# Overcurrent_Protection.net
KiCad netlist of a schematic drawn in Altium Designer
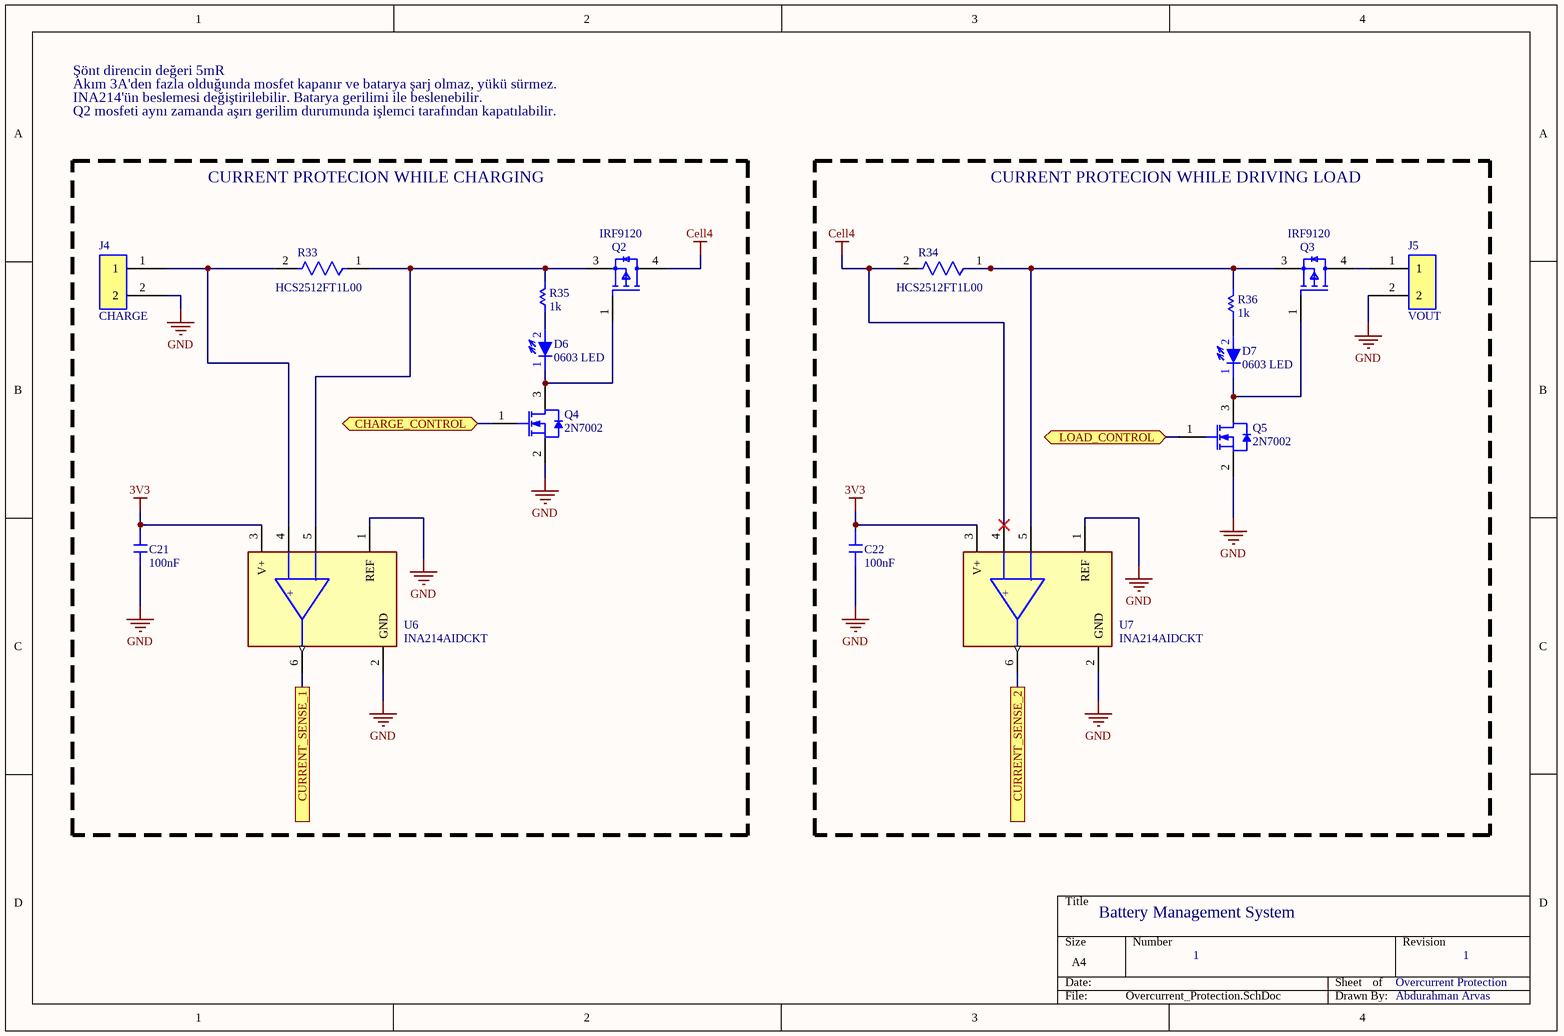
[diagram p0: Overcurrent_Protection.SchDoc]

(export (version "E")
  (design (tool "Eeschema 10.0.6"))
  (components
    (comp (ref "C21")
      (value "100nF")
      (footprint "C0805")
      (libsource (lib "Arvas_AltiumSCH") (part "SMD_Capacitor"))
    )
    (comp (ref "C22")
      (value "100nF")
      (footprint "C0805")
      (libsource (lib "Arvas_AltiumSCH") (part "SMD_Capacitor"))
    )
    (comp (ref "D6")
      (value "0603 LED")
      (footprint "LED_0603")
      (description "Light Emitting Diode with 0603 footprint.")
      (libsource (lib "Arvas_AltiumSCH") (part "Led 0603"))
    )
    (comp (ref "D7")
      (value "0603 LED")
      (footprint "LED_0603")
      (description "Light Emitting Diode with 0603 footprint.")
      (libsource (lib "Arvas_AltiumSCH") (part "Led 0603"))
    )
    (comp (ref "J4")
      (value "CHARGE")
      (footprint "CONN X2")
      (description "İki Pin Connector")
      (libsource (lib "Arvas_AltiumSCH") (part "CONN X2"))
    )
    (comp (ref "J5")
      (value "VOUT")
      (footprint "CONN X2")
      (description "İki Pin Connector")
      (libsource (lib "Arvas_AltiumSCH") (part "CONN X2"))
    )
    (comp (ref "Q2")
      (value "IRF9120")
      (footprint "FP-TO-252-MFG")
      (description "MOSFET P-CHANNEL 60V 20A TO252")
      (libsource (lib "Altium Content Vault") (part "20f9a20c5713cc6515f41ebd1ff0572"))
    )
    (comp (ref "Q3")
      (value "IRF9120")
      (footprint "FP-TO-252-MFG")
      (description "MOSFET P-CHANNEL 60V 20A TO252")
      (libsource (lib "Altium Content Vault") (part "20f9a20c5713cc6515f41ebd1ff0572"))
    )
    (comp (ref "Q4")
      (value "2N7002")
      (footprint "STM-SOT-23-3_V")
      (description "N-channel 60 V, 1.8 Ohm, 0.35 A STripFET(TM) II Power MOSFET, SOT23")
      (fields (field (name "MANUFACTURER") "STMicroelectronics"))
      (libsource (lib "Altium Content Vault") (part "STM-NEMOS-G1S2D3-3"))
    )
    (comp (ref "Q5")
      (value "2N7002")
      (footprint "STM-SOT-23-3_V")
      (description "N-channel 60 V, 1.8 Ohm, 0.35 A STripFET(TM) II Power MOSFET, SOT23")
      (fields (field (name "MANUFACTURER") "STMicroelectronics"))
      (libsource (lib "Altium Content Vault") (part "STM-NEMOS-G1S2D3-3"))
    )
    (comp (ref "R33")
      (value "HCS2512FT1L00")
      (footprint "FP-HCS2512FT1L00-MFG")
      (description "RES 0.001 OHM 1% 3W 2512")
      (fields (field (name "TOLERANCE") "1%"))
      (libsource (lib "Altium Content Vault") (part "1029c3af85768c4190bb7ad29bc67b5"))
    )
    (comp (ref "R34")
      (value "HCS2512FT1L00")
      (footprint "FP-HCS2512FT1L00-MFG")
      (description "RES 0.001 OHM 1% 3W 2512")
      (fields (field (name "TOLERANCE") "1%"))
      (libsource (lib "Altium Content Vault") (part "1029c3af85768c4190bb7ad29bc67b5"))
    )
    (comp (ref "R35")
      (value "1k")
      (footprint "R0805")
      (description "SMD Chip Resistor")
      (libsource (lib "Arvas_AltiumSCH") (part "SMD Resistor"))
    )
    (comp (ref "R36")
      (value "1k")
      (footprint "R0805")
      (description "SMD Chip Resistor")
      (libsource (lib "Arvas_AltiumSCH") (part "SMD Resistor"))
    )
    (comp (ref "U6")
      (value "INA214AIDCKT")
      (footprint "FP-DCK0006A-MFG")
      (description "IC CURR SENSE 1 CIRCUIT SC70-6")
      (fields
        (field (name "MANUFACTURER") "Texas Instruments")
        (field (name "OCTOPART") "https://octopart.com/ina214aidckt-texas+instruments-7830703")
      )
      (libsource (lib "Altium Content Vault") (part "c10d82c028949ab116d50aa41bcba86"))
    )
    (comp (ref "U7")
      (value "INA214AIDCKT")
      (footprint "FP-DCK0006A-MFG")
      (description "IC CURR SENSE 1 CIRCUIT SC70-6")
      (fields
        (field (name "MANUFACTURER") "Texas Instruments")
        (field (name "OCTOPART") "https://octopart.com/ina214aidckt-texas+instruments-7830703")
      )
      (libsource (lib "Altium Content Vault") (part "c10d82c028949ab116d50aa41bcba86"))
    )
  )
  (nets
    (net (code "1") (name "/CHARGE_CONTROL") (class "Default")
      (node (ref "Q4") (pin "1") (pinfunction "G_1") (pintype "passive"))
    )
    (net (code "2") (name "/CURRENT_SENSE_1") (class "Default")
      (node (ref "U6") (pin "6") (pinfunction "OUT_6") (pintype "output"))
    )
    (net (code "3") (name "/CURRENT_SENSE_2") (class "Default")
      (node (ref "U7") (pin "6") (pinfunction "OUT_6") (pintype "output"))
    )
    (net (code "4") (name "/LOAD_CONTROL") (class "Default")
      (node (ref "Q5") (pin "1") (pinfunction "G_1") (pintype "passive"))
    )
    (net (code "5") (name "3V3") (class "Default")
      (node (ref "C21") (pin "2") (pinfunction "2_2") (pintype "passive"))
      (node (ref "C22") (pin "2") (pinfunction "2_2") (pintype "passive"))
      (node (ref "U6") (pin "3") (pinfunction "V+_3") (pintype "power_in"))
      (node (ref "U7") (pin "3") (pinfunction "V+_3") (pintype "power_in"))
    )
    (net (code "6") (name "Cell4") (class "Default")
      (node (ref "Q2") (pin "4") (pinfunction "Drain_4") (pintype "passive"))
      (node (ref "R34") (pin "2") (pinfunction "2_2") (pintype "passive"))
      (node (ref "U7") (pin "4") (pinfunction "IN+_4") (pintype "tri_state"))
    )
    (net (code "7") (name "GND") (class "Default")
      (node (ref "C21") (pin "1") (pinfunction "1_1") (pintype "passive"))
      (node (ref "C22") (pin "1") (pinfunction "1_1") (pintype "passive"))
      (node (ref "J4") (pin "2") (pinfunction "2_2") (pintype "passive"))
      (node (ref "J5") (pin "2") (pinfunction "2_2") (pintype "passive"))
      (node (ref "Q4") (pin "2") (pinfunction "S_2") (pintype "passive"))
      (node (ref "Q5") (pin "2") (pinfunction "S_2") (pintype "passive"))
      (node (ref "U6") (pin "1") (pinfunction "REF_1") (pintype "passive"))
      (node (ref "U6") (pin "2") (pinfunction "GND_2") (pintype "power_in"))
      (node (ref "U7") (pin "1") (pinfunction "REF_1") (pintype "passive"))
      (node (ref "U7") (pin "2") (pinfunction "GND_2") (pintype "power_in"))
    )
    (net (code "8") (name "Net-(D6-Anode)") (class "Default")
      (node (ref "D6") (pin "2") (pinfunction "Anode_2") (pintype "passive"))
      (node (ref "R35") (pin "1") (pinfunction "1_1") (pintype "passive"))
    )
    (net (code "9") (name "Net-(D6-Cathode)") (class "Default")
      (node (ref "D6") (pin "1") (pinfunction "Cathode_1") (pintype "passive"))
      (node (ref "Q2") (pin "1") (pinfunction "Gate_1") (pintype "passive"))
      (node (ref "Q4") (pin "3") (pinfunction "D_3") (pintype "passive"))
    )
    (net (code "10") (name "Net-(D7-Anode)") (class "Default")
      (node (ref "D7") (pin "2") (pinfunction "Anode_2") (pintype "passive"))
      (node (ref "R36") (pin "1") (pinfunction "1_1") (pintype "passive"))
    )
    (net (code "11") (name "Net-(D7-Cathode)") (class "Default")
      (node (ref "D7") (pin "1") (pinfunction "Cathode_1") (pintype "passive"))
      (node (ref "Q3") (pin "1") (pinfunction "Gate_1") (pintype "passive"))
      (node (ref "Q5") (pin "3") (pinfunction "D_3") (pintype "passive"))
    )
    (net (code "12") (name "Net-(Q2-Source)") (class "Default")
      (node (ref "Q2") (pin "3") (pinfunction "Source_3") (pintype "passive"))
      (node (ref "R33") (pin "1") (pinfunction "1_1") (pintype "passive"))
      (node (ref "R35") (pin "2") (pinfunction "2_2") (pintype "passive"))
      (node (ref "U6") (pin "5") (pinfunction "IN-_5") (pintype "tri_state"))
    )
    (net (code "13") (name "Net-(Q3-Drain)") (class "Default")
      (node (ref "J5") (pin "1") (pinfunction "1_1") (pintype "passive"))
      (node (ref "Q3") (pin "4") (pinfunction "Drain_4") (pintype "passive"))
    )
    (net (code "14") (name "Net-(Q3-Source)") (class "Default")
      (node (ref "Q3") (pin "3") (pinfunction "Source_3") (pintype "passive"))
      (node (ref "R34") (pin "1") (pinfunction "1_1") (pintype "passive"))
      (node (ref "R36") (pin "2") (pinfunction "2_2") (pintype "passive"))
      (node (ref "U7") (pin "5") (pinfunction "IN-_5") (pintype "tri_state"))
    )
    (net (code "15") (name "Net-(U6-IN+)") (class "Default")
      (node (ref "J4") (pin "1") (pinfunction "1_1") (pintype "passive"))
      (node (ref "R33") (pin "2") (pinfunction "2_2") (pintype "passive"))
      (node (ref "U6") (pin "4") (pinfunction "IN+_4") (pintype "tri_state"))
    )
  )
)
